# North_Paw_V2p1.net
KiCad netlist of a schematic drawn in EAGLE
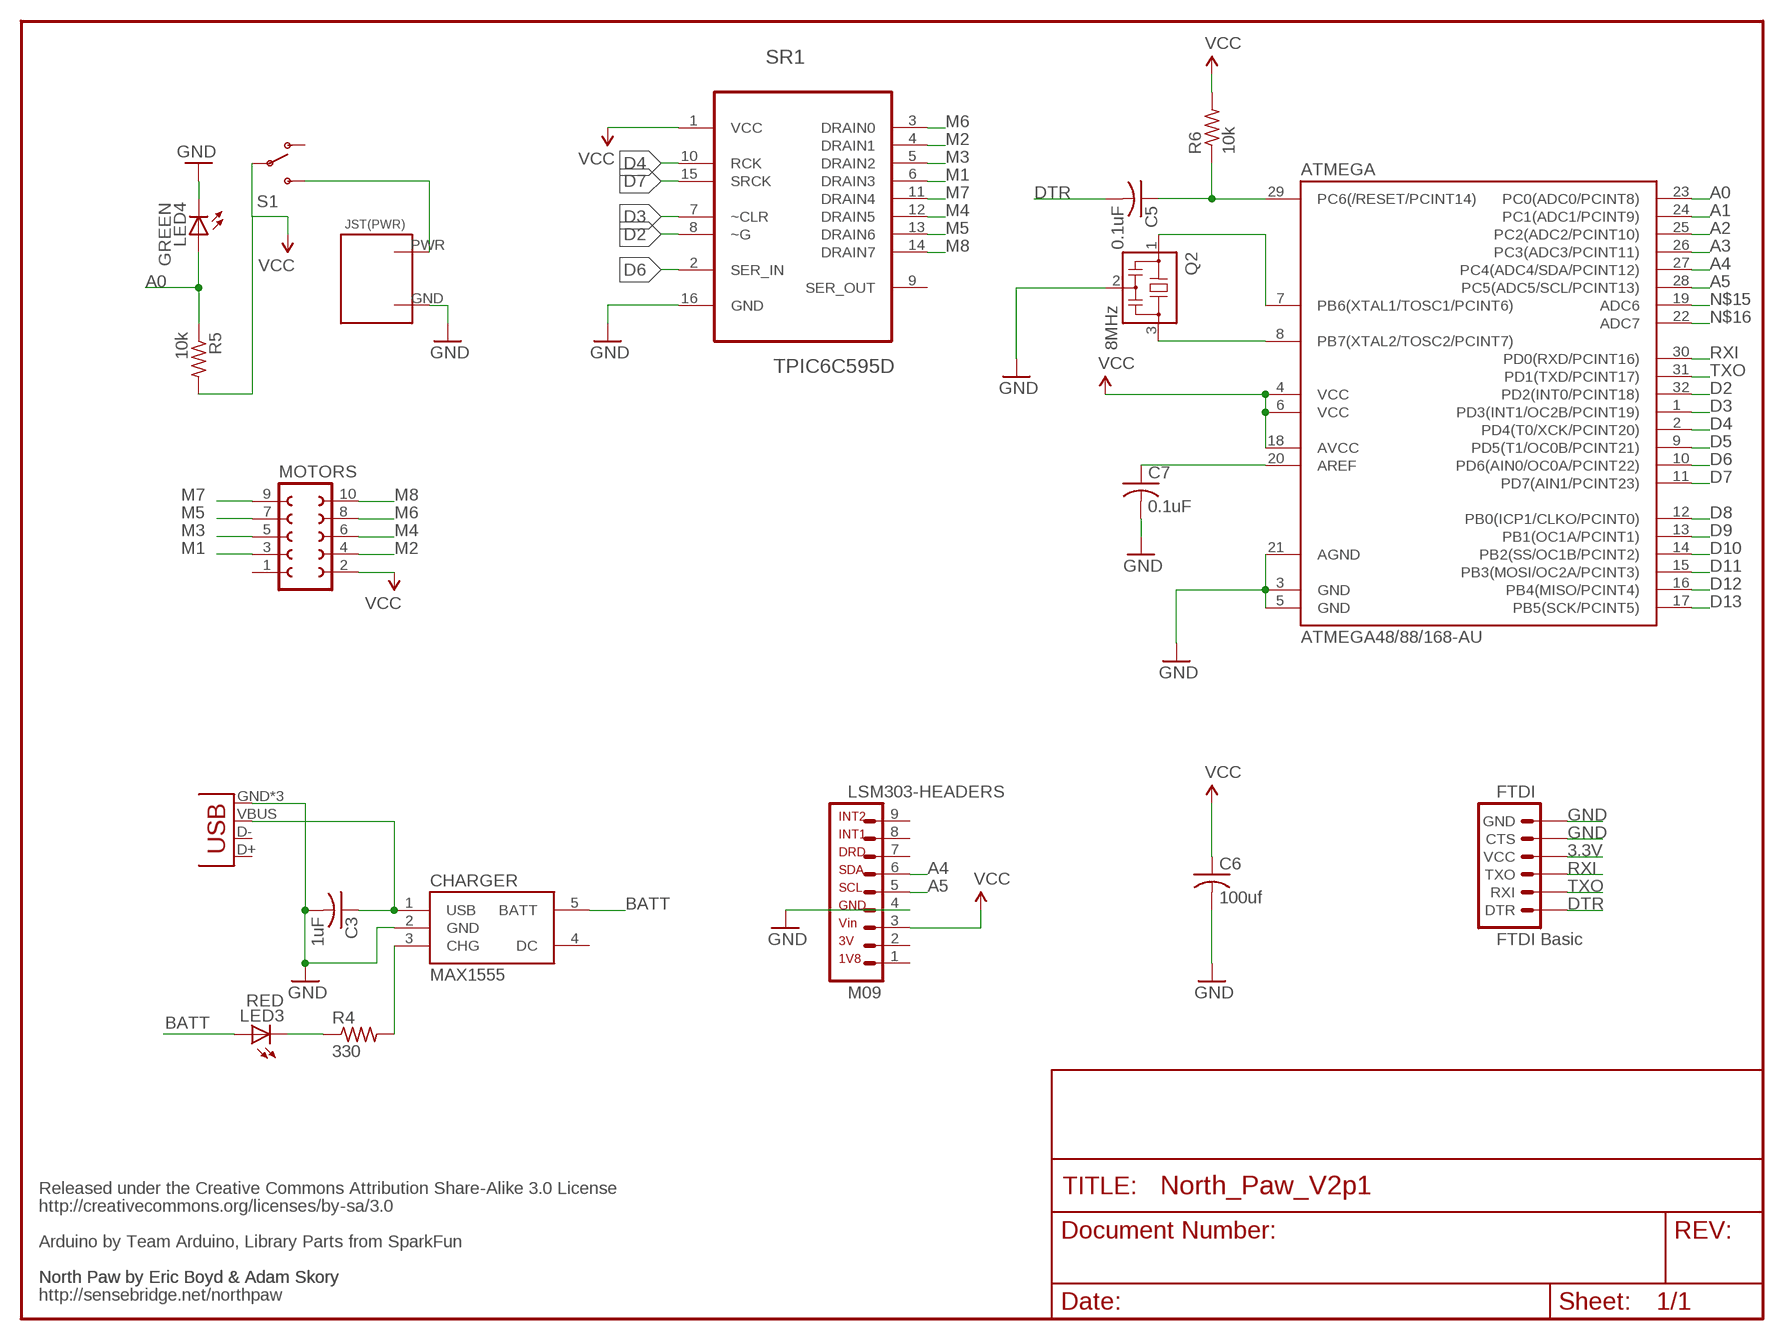
[diagram p0: schematic, sheet 1]

(export (version "E")
  (design (tool "Eeschema 10.0.6"))
  (components
    (comp (ref "ATMEGA")
      (value "ATMEGA48/88/168-AU")
      (footprint "eagle-import:TQFP32-08")
      (libsource (lib "eagle-import") (part "ATMEGA48/88/168-AU"))
    )
    (comp (ref "C3")
      (value "1uF")
      (footprint "eagle-import:C0805")
      (fields (field (name "MF") "KEMET") (field (name "MPN") "C0805C105K4RACTU"))
      (libsource (lib "eagle-import") (part "C-USC0805"))
    )
    (comp (ref "C5")
      (value "0.1uF")
      (footprint "eagle-import:C0805")
      (fields (field (name "MPN") "C0805C104K3RACTU"))
      (libsource (lib "eagle-import") (part "C-USC0805"))
    )
    (comp (ref "C6")
      (value "100uf")
      (footprint "eagle-import:C0805")
      (fields (field (name "MPN") "TLCR107M004XTA"))
      (libsource (lib "eagle-import") (part "C-USC0805"))
    )
    (comp (ref "C7")
      (value "0.1uF")
      (footprint "eagle-import:C0805")
      (fields (field (name "MPN") "C0805C104K3RACTU"))
      (libsource (lib "eagle-import") (part "C-USC0805"))
    )
    (comp (ref "CHARGER")
      (value "MAX1555")
      (footprint "eagle-import:SOT23-5")
      (fields (field (name "MPN") "MAX1555EZK+T."))
      (libsource (lib "eagle-import") (part "MAX1555"))
    )
    (comp (ref "FTDI")
      (value "FTDI Basic")
      (footprint "eagle-import:1X06")
      (libsource (lib "eagle-import") (part "ARDUINO_SERIAL_PROGRAMPTH"))
    )
    (comp (ref "JP1")
      (value "USB-MICROB")
      (footprint "eagle-import:USB-MICROB")
      (libsource (lib "eagle-import") (part "USB-MICROB"))
    )
    (comp (ref "JST(PWR)")
      (value "S2B-PH-K-S")
      (footprint "eagle-import:S4B-ZR")
      (libsource (lib "eagle-import") (part "S2B-PH-K-S"))
    )
    (comp (ref "LED3")
      (value "RED")
      (footprint "eagle-import:CHIP-LED0805")
      (fields (field (name "MPN") "150080RS75000"))
      (libsource (lib "eagle-import") (part "LEDCHIP-LED0805"))
    )
    (comp (ref "LED4")
      (value "GREEN")
      (footprint "eagle-import:CHIP-LED0805")
      (fields (field (name "MPN") "150080GS75000"))
      (libsource (lib "eagle-import") (part "LEDCHIP-LED0805"))
    )
    (comp (ref "LSM303-HEADERS")
      (value "M09")
      (footprint "eagle-import:MA09-1W")
      (libsource (lib "eagle-import") (part "MA09-1W"))
    )
    (comp (ref "MOTORS")
      (value "FE05-2")
      (footprint "eagle-import:FE05-2")
      (libsource (lib "eagle-import") (part "FE05-2"))
    )
    (comp (ref "Q2")
      (value "8MHz")
      (footprint "eagle-import:CSTCR6M")
      (fields (field (name "MPN") "CSTCR6M00G53-R0"))
      (libsource (lib "eagle-import") (part "CSTCR6M00G53Z"))
    )
    (comp (ref "R4")
      (value "330")
      (footprint "eagle-import:R0805")
      (fields (field (name "MPN") "CRCW0805330RJNEA"))
      (libsource (lib "eagle-import") (part "R-US_R0805"))
    )
    (comp (ref "R5")
      (value "10k")
      (footprint "eagle-import:R0805")
      (fields (field (name "MF") "VISHAY/DALE") (field (name "MPN") "CRCW080510K0FKTA"))
      (libsource (lib "eagle-import") (part "R-US_R0805"))
    )
    (comp (ref "R6")
      (value "10k")
      (footprint "eagle-import:R0805")
      (fields (field (name "MF") "VISHAY/DALE") (field (name "MPN") "CRCW080510K0FKTA"))
      (libsource (lib "eagle-import") (part "R-US_R0805"))
    )
    (comp (ref "S1")
      (value "SWITCH-SPDT-SMD-A")
      (footprint "eagle-import:SWITCH-SPST-SMD-A")
      (libsource (lib "eagle-import") (part "SWITCH-SPDT-SMD-A"))
    )
    (comp (ref "SR1")
      (value "TPIC6C595D")
      (footprint "eagle-import:SOIC127P600X175-16N")
      (fields (field (name "MF") "TEXAS INSTRUMENTS"))
      (libsource (lib "eagle-import") (part "TPIC6C595D"))
    )
  )
  (nets
    (net (code "1") (name "/A0") (class "Default")
      (node (ref "ATMEGA") (pin "23") (pinfunction "PC0(ADC0/PCINT8)_23") (pintype "bidirectional"))
      (node (ref "LED4") (pin "A") (pinfunction "A_A") (pintype "passive"))
      (node (ref "R5") (pin "1") (pinfunction "1_1") (pintype "passive"))
    )
    (net (code "2") (name "/A1") (class "Default")
      (node (ref "ATMEGA") (pin "24") (pinfunction "PC1(ADC1/PCINT9)_24") (pintype "bidirectional"))
    )
    (net (code "3") (name "/A2") (class "Default")
      (node (ref "ATMEGA") (pin "25") (pinfunction "PC2(ADC2/PCINT10)_25") (pintype "bidirectional"))
    )
    (net (code "4") (name "/A3") (class "Default")
      (node (ref "ATMEGA") (pin "26") (pinfunction "PC3(ADC3/PCINT11)_26") (pintype "bidirectional"))
    )
    (net (code "5") (name "/A4") (class "Default")
      (node (ref "ATMEGA") (pin "27") (pinfunction "PC4(ADC4/SDA/PCINT12)_27") (pintype "bidirectional"))
      (node (ref "LSM303-HEADERS") (pin "6") (pinfunction "6_6") (pintype "passive"))
    )
    (net (code "6") (name "/A5") (class "Default")
      (node (ref "ATMEGA") (pin "28") (pinfunction "PC5(ADC5/SCL/PCINT13)_28") (pintype "bidirectional"))
      (node (ref "LSM303-HEADERS") (pin "5") (pinfunction "5_5") (pintype "passive"))
    )
    (net (code "7") (name "/BATT") (class "Default")
      (node (ref "CHARGER") (pin "5") (pinfunction "BATT_5") (pintype "bidirectional"))
      (node (ref "LED3") (pin "A") (pinfunction "A_A") (pintype "passive"))
    )
    (net (code "8") (name "/D5") (class "Default")
      (node (ref "ATMEGA") (pin "9") (pinfunction "PD5(T1/OC0B/PCINT21)_9") (pintype "bidirectional"))
    )
    (net (code "9") (name "/D8") (class "Default")
      (node (ref "ATMEGA") (pin "12") (pinfunction "PB0(ICP1/CLKO/PCINT0)_12") (pintype "bidirectional"))
    )
    (net (code "10") (name "/D9") (class "Default")
      (node (ref "ATMEGA") (pin "13") (pinfunction "PB1(OC1A/PCINT1)_13") (pintype "bidirectional"))
    )
    (net (code "11") (name "/D10") (class "Default")
      (node (ref "ATMEGA") (pin "14") (pinfunction "PB2(SS/OC1B/PCINT2)_14") (pintype "bidirectional"))
    )
    (net (code "12") (name "/D11") (class "Default")
      (node (ref "ATMEGA") (pin "15") (pinfunction "PB3(MOSI/OC2A/PCINT3)_15") (pintype "bidirectional"))
    )
    (net (code "13") (name "/D12") (class "Default")
      (node (ref "ATMEGA") (pin "16") (pinfunction "PB4(MISO/PCINT4)_16") (pintype "bidirectional"))
    )
    (net (code "14") (name "/D13") (class "Default")
      (node (ref "ATMEGA") (pin "17") (pinfunction "PB5(SCK/PCINT5)_17") (pintype "bidirectional"))
    )
    (net (code "15") (name "/DTR") (class "Default")
      (node (ref "C5") (pin "2") (pinfunction "2_2") (pintype "passive"))
      (node (ref "FTDI") (pin "1") (pinfunction "DTR_1") (pintype "passive"))
    )
    (net (code "16") (name "/M1") (class "Default")
      (node (ref "MOTORS") (pin "3") (pinfunction "3_3") (pintype "passive"))
      (node (ref "SR1") (pin "6") (pinfunction "DRAIN3_6") (pintype "output"))
    )
    (net (code "17") (name "/M2") (class "Default")
      (node (ref "MOTORS") (pin "4") (pinfunction "4_4") (pintype "passive"))
      (node (ref "SR1") (pin "4") (pinfunction "DRAIN1_4") (pintype "output"))
    )
    (net (code "18") (name "/M3") (class "Default")
      (node (ref "MOTORS") (pin "5") (pinfunction "5_5") (pintype "passive"))
      (node (ref "SR1") (pin "5") (pinfunction "DRAIN2_5") (pintype "output"))
    )
    (net (code "19") (name "/M4") (class "Default")
      (node (ref "MOTORS") (pin "6") (pinfunction "6_6") (pintype "passive"))
      (node (ref "SR1") (pin "12") (pinfunction "DRAIN5_12") (pintype "output"))
    )
    (net (code "20") (name "/M5") (class "Default")
      (node (ref "MOTORS") (pin "7") (pinfunction "7_7") (pintype "passive"))
      (node (ref "SR1") (pin "13") (pinfunction "DRAIN6_13") (pintype "output"))
    )
    (net (code "21") (name "/M6") (class "Default")
      (node (ref "MOTORS") (pin "8") (pinfunction "8_8") (pintype "passive"))
      (node (ref "SR1") (pin "3") (pinfunction "DRAIN0_3") (pintype "output"))
    )
    (net (code "22") (name "/M7") (class "Default")
      (node (ref "MOTORS") (pin "9") (pinfunction "9_9") (pintype "passive"))
      (node (ref "SR1") (pin "11") (pinfunction "DRAIN4_11") (pintype "output"))
    )
    (net (code "23") (name "/M8") (class "Default")
      (node (ref "MOTORS") (pin "10") (pinfunction "10_10") (pintype "passive"))
      (node (ref "SR1") (pin "14") (pinfunction "DRAIN7_14") (pintype "output"))
    )
    (net (code "24") (name "/N$15") (class "Default")
      (node (ref "ATMEGA") (pin "19") (pinfunction "ADC6_19") (pintype "passive"))
    )
    (net (code "25") (name "/N$16") (class "Default")
      (node (ref "ATMEGA") (pin "22") (pinfunction "ADC7_22") (pintype "passive"))
    )
    (net (code "26") (name "/RXI") (class "Default")
      (node (ref "ATMEGA") (pin "30") (pinfunction "PD0(RXD/PCINT16)_30") (pintype "bidirectional"))
      (node (ref "FTDI") (pin "3") (pinfunction "TXO_3") (pintype "passive"))
    )
    (net (code "27") (name "/TXO") (class "Default")
      (node (ref "ATMEGA") (pin "31") (pinfunction "PD1(TXD/PCINT17)_31") (pintype "bidirectional"))
      (node (ref "FTDI") (pin "2") (pinfunction "RXI_2") (pintype "passive"))
    )
    (net (code "28") (name "D2") (class "Default")
      (node (ref "ATMEGA") (pin "32") (pinfunction "PD2(INT0/PCINT18)_32") (pintype "bidirectional"))
      (node (ref "SR1") (pin "8") (pinfunction "~{G}_8") (pintype "input"))
    )
    (net (code "29") (name "D3") (class "Default")
      (node (ref "ATMEGA") (pin "1") (pinfunction "PD3(INT1/OC2B/PCINT19)_1") (pintype "bidirectional"))
      (node (ref "SR1") (pin "7") (pinfunction "~{CLR}_7") (pintype "input"))
    )
    (net (code "30") (name "D4") (class "Default")
      (node (ref "ATMEGA") (pin "2") (pinfunction "PD4(T0/XCK/PCINT20)_2") (pintype "bidirectional"))
      (node (ref "SR1") (pin "10") (pinfunction "RCK_10") (pintype "input"))
    )
    (net (code "31") (name "D6") (class "Default")
      (node (ref "ATMEGA") (pin "10") (pinfunction "PD6(AIN0/OC0A/PCINT22)_10") (pintype "bidirectional"))
      (node (ref "SR1") (pin "2") (pinfunction "SER_IN_2") (pintype "input"))
    )
    (net (code "32") (name "D7") (class "Default")
      (node (ref "ATMEGA") (pin "11") (pinfunction "PD7(AIN1/PCINT23)_11") (pintype "bidirectional"))
      (node (ref "SR1") (pin "15") (pinfunction "SRCK_15") (pintype "input"))
    )
    (net (code "33") (name "GND") (class "Default")
      (node (ref "ATMEGA") (pin "21") (pinfunction "AGND_21") (pintype "power_in"))
      (node (ref "ATMEGA") (pin "3") (pinfunction "GND_3") (pintype "power_in"))
      (node (ref "ATMEGA") (pin "5") (pinfunction "GND_5") (pintype "power_in"))
      (node (ref "C3") (pin "2") (pinfunction "2_2") (pintype "passive"))
      (node (ref "C6") (pin "2") (pinfunction "2_2") (pintype "passive"))
      (node (ref "C7") (pin "2") (pinfunction "2_2") (pintype "passive"))
      (node (ref "CHARGER") (pin "2") (pinfunction "GND_2") (pintype "bidirectional"))
      (node (ref "FTDI") (pin "5") (pinfunction "CTS_5") (pintype "passive"))
      (node (ref "FTDI") (pin "6") (pinfunction "GND_6") (pintype "passive"))
      (node (ref "JP1") (pin "GND") (pinfunction "GND_GND") (pintype "bidirectional"))
      (node (ref "JP1") (pin "MT1") (pinfunction "GND_MT1") (pintype "bidirectional"))
      (node (ref "JP1") (pin "MT2") (pinfunction "GND_MT2") (pintype "bidirectional"))
      (node (ref "JST(PWR)") (pin "GND") (pinfunction "GND_GND") (pintype "power_in"))
      (node (ref "LED4") (pin "C") (pinfunction "C_C") (pintype "passive"))
      (node (ref "LSM303-HEADERS") (pin "4") (pinfunction "4_4") (pintype "passive"))
      (node (ref "Q2") (pin "2") (pinfunction "2_2") (pintype "passive"))
      (node (ref "SR1") (pin "16") (pinfunction "GND_16") (pintype "passive"))
    )
    (net (code "34") (name "Net-(ATMEGA-AREF)") (class "Default")
      (node (ref "ATMEGA") (pin "20") (pinfunction "AREF_20") (pintype "passive"))
      (node (ref "C7") (pin "1") (pinfunction "1_1") (pintype "passive"))
    )
    (net (code "35") (name "Net-(ATMEGA-PB6(XTAL1{slash}TOSC1{slash}PCINT6))") (class "Default")
      (node (ref "ATMEGA") (pin "7") (pinfunction "PB6(XTAL1/TOSC1/PCINT6)_7") (pintype "bidirectional"))
      (node (ref "Q2") (pin "1") (pinfunction "1_1") (pintype "passive"))
    )
    (net (code "36") (name "Net-(ATMEGA-PB7(XTAL2{slash}TOSC2{slash}PCINT7))") (class "Default")
      (node (ref "ATMEGA") (pin "8") (pinfunction "PB7(XTAL2/TOSC2/PCINT7)_8") (pintype "bidirectional"))
      (node (ref "Q2") (pin "3") (pinfunction "3_3") (pintype "passive"))
    )
    (net (code "37") (name "Net-(ATMEGA-PC6({slash}RESET{slash}PCINT14))") (class "Default")
      (node (ref "ATMEGA") (pin "29") (pinfunction "PC6(/RESET/PCINT14)_29") (pintype "bidirectional"))
      (node (ref "C5") (pin "1") (pinfunction "1_1") (pintype "passive"))
      (node (ref "R6") (pin "1") (pinfunction "1_1") (pintype "passive"))
    )
    (net (code "38") (name "Net-(CHARGER-CHG)") (class "Default")
      (node (ref "CHARGER") (pin "3") (pinfunction "CHG_3") (pintype "bidirectional"))
      (node (ref "R4") (pin "2") (pinfunction "2_2") (pintype "passive"))
    )
    (net (code "39") (name "Net-(CHARGER-USB)") (class "Default")
      (node (ref "C3") (pin "1") (pinfunction "1_1") (pintype "passive"))
      (node (ref "CHARGER") (pin "1") (pinfunction "USB_1") (pintype "bidirectional"))
      (node (ref "JP1") (pin "VBUS") (pinfunction "VBUS_VBUS") (pintype "bidirectional"))
    )
    (net (code "40") (name "Net-(LED3-PadC)") (class "Default")
      (node (ref "LED3") (pin "C") (pinfunction "C_C") (pintype "passive"))
      (node (ref "R4") (pin "1") (pinfunction "1_1") (pintype "passive"))
    )
    (net (code "41") (name "Net-(S1-S)") (class "Default")
      (node (ref "JST(PWR)") (pin "PWR") (pinfunction "PWR_PWR") (pintype "power_in"))
      (node (ref "S1") (pin "3") (pinfunction "S_3") (pintype "passive"))
    )
    (net (code "42") (name "VCC") (class "Default")
      (node (ref "ATMEGA") (pin "18") (pinfunction "AVCC_18") (pintype "passive"))
      (node (ref "ATMEGA") (pin "4") (pinfunction "VCC_4") (pintype "power_in"))
      (node (ref "ATMEGA") (pin "6") (pinfunction "VCC_6") (pintype "power_in"))
      (node (ref "C6") (pin "1") (pinfunction "1_1") (pintype "passive"))
      (node (ref "FTDI") (pin "4") (pinfunction "VCC_4") (pintype "passive"))
      (node (ref "LSM303-HEADERS") (pin "3") (pinfunction "3_3") (pintype "passive"))
      (node (ref "MOTORS") (pin "2") (pinfunction "2_2") (pintype "passive"))
      (node (ref "R5") (pin "2") (pinfunction "2_2") (pintype "passive"))
      (node (ref "R6") (pin "2") (pinfunction "2_2") (pintype "passive"))
      (node (ref "S1") (pin "2") (pinfunction "P_2") (pintype "passive"))
      (node (ref "SR1") (pin "1") (pinfunction "VCC_1") (pintype "power_in"))
    )
    (net (code "43") (name "unconnected-(CHARGER-DC-Pad4)") (class "Default")
      (node (ref "CHARGER") (pin "4") (pinfunction "DC_4") (pintype "bidirectional"))
    )
    (net (code "44") (name "unconnected-(JP1-PadD+)") (class "Default")
      (node (ref "JP1") (pin "D+") (pinfunction "D+_D+") (pintype "bidirectional"))
    )
    (net (code "45") (name "unconnected-(JP1-PadD-)") (class "Default")
      (node (ref "JP1") (pin "D-") (pinfunction "D-_D-") (pintype "bidirectional"))
    )
    (net (code "46") (name "unconnected-(LSM303-HEADERS-Pad1)") (class "Default")
      (node (ref "LSM303-HEADERS") (pin "1") (pinfunction "1_1") (pintype "passive"))
    )
    (net (code "47") (name "unconnected-(LSM303-HEADERS-Pad2)") (class "Default")
      (node (ref "LSM303-HEADERS") (pin "2") (pinfunction "2_2") (pintype "passive"))
    )
    (net (code "48") (name "unconnected-(LSM303-HEADERS-Pad7)") (class "Default")
      (node (ref "LSM303-HEADERS") (pin "7") (pinfunction "7_7") (pintype "passive"))
    )
    (net (code "49") (name "unconnected-(LSM303-HEADERS-Pad8)") (class "Default")
      (node (ref "LSM303-HEADERS") (pin "8") (pinfunction "8_8") (pintype "passive"))
    )
    (net (code "50") (name "unconnected-(LSM303-HEADERS-Pad9)") (class "Default")
      (node (ref "LSM303-HEADERS") (pin "9") (pinfunction "9_9") (pintype "passive"))
    )
    (net (code "51") (name "unconnected-(MOTORS-Pad1)") (class "Default")
      (node (ref "MOTORS") (pin "1") (pinfunction "1_1") (pintype "passive"))
    )
    (net (code "52") (name "unconnected-(S1-O-Pad1)") (class "Default")
      (node (ref "S1") (pin "1") (pinfunction "O_1") (pintype "passive"))
    )
    (net (code "53") (name "unconnected-(SR1-SER_OUT-Pad9)") (class "Default")
      (node (ref "SR1") (pin "9") (pinfunction "SER_OUT_9") (pintype "output"))
    )
  )
)
